# amp_tda2030_2ch_otl.net
KiCad netlist of a schematic drawn in EAGLE
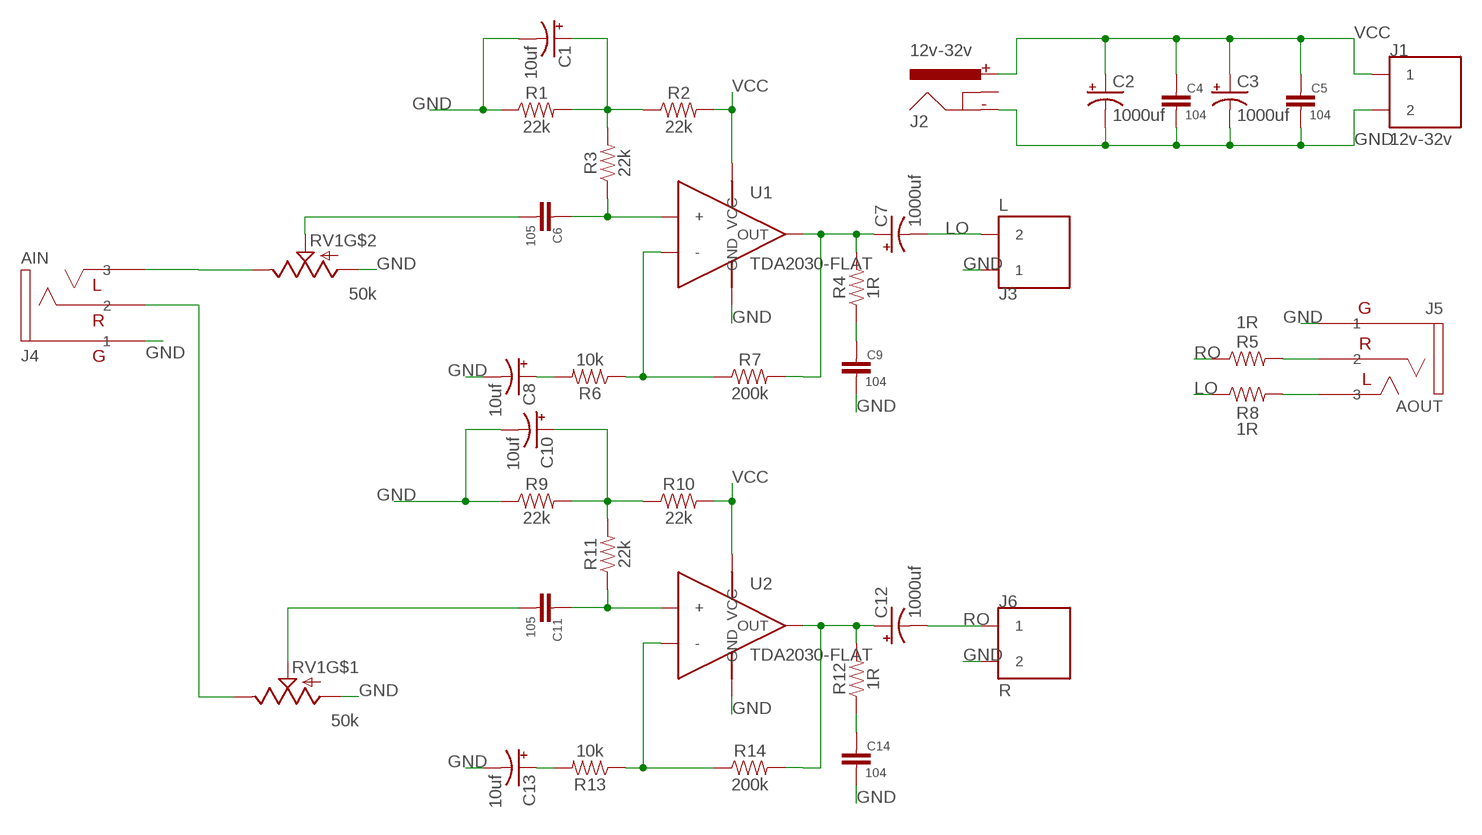
[diagram p0: schematic, sheet 1]

(export (version "E")
  (design (tool "Eeschema 10.0.6"))
  (components
    (comp (ref "C1")
      (value "10uf")
      (footprint "eagle-import:CAP_2.5MM")
      (libsource (lib "eagle-import") (part "CAP"))
    )
    (comp (ref "C2")
      (value "1000uf")
      (footprint "eagle-import:CAP_5MM_10D")
      (libsource (lib "eagle-import") (part "CAP5MM"))
    )
    (comp (ref "C3")
      (value "1000uf")
      (footprint "eagle-import:CAP_5MM_10D")
      (libsource (lib "eagle-import") (part "CAP5MM"))
    )
    (comp (ref "C4")
      (value "104")
      (footprint "eagle-import:CAP_5MM")
      (libsource (lib "eagle-import") (part "CAP_P"))
    )
    (comp (ref "C5")
      (value "104")
      (footprint "eagle-import:CAP_5MM")
      (libsource (lib "eagle-import") (part "CAP_P"))
    )
    (comp (ref "C6")
      (value "105")
      (footprint "eagle-import:CAP_5MM")
      (libsource (lib "eagle-import") (part "CAP_P"))
    )
    (comp (ref "C7")
      (value "1000uf")
      (footprint "eagle-import:CAP_5MM_10D")
      (libsource (lib "eagle-import") (part "CAP5MM"))
    )
    (comp (ref "C8")
      (value "10uf")
      (footprint "eagle-import:CAP_2.5MM")
      (libsource (lib "eagle-import") (part "CAP"))
    )
    (comp (ref "C9")
      (value "104")
      (footprint "eagle-import:CAP_5MM")
      (libsource (lib "eagle-import") (part "CAP_P"))
    )
    (comp (ref "C10")
      (value "10uf")
      (footprint "eagle-import:CAP_2.5MM")
      (libsource (lib "eagle-import") (part "CAP"))
    )
    (comp (ref "C11")
      (value "105")
      (footprint "eagle-import:CAP_5MM")
      (libsource (lib "eagle-import") (part "CAP_P"))
    )
    (comp (ref "C12")
      (value "1000uf")
      (footprint "eagle-import:CAP_5MM_10D")
      (libsource (lib "eagle-import") (part "CAP5MM"))
    )
    (comp (ref "C13")
      (value "10uf")
      (footprint "eagle-import:CAP_2.5MM")
      (libsource (lib "eagle-import") (part "CAP"))
    )
    (comp (ref "C14")
      (value "104")
      (footprint "eagle-import:CAP_5MM")
      (libsource (lib "eagle-import") (part "CAP_P"))
    )
    (comp (ref "J1")
      (value "12v-32v")
      (footprint "eagle-import:2P_5.08MM")
      (libsource (lib "eagle-import") (part "2P5.0"))
    )
    (comp (ref "J2")
      (value "12v-32v")
      (footprint "eagle-import:POWER_JACK_PTH_LOCK")
      (libsource (lib "eagle-import") (part "POWER_JACKPTH_LOCK"))
    )
    (comp (ref "J3")
      (value "L")
      (footprint "eagle-import:2P_5.08MM")
      (libsource (lib "eagle-import") (part "2P5.0"))
    )
    (comp (ref "J4")
      (value "AIN")
      (footprint "eagle-import:3.5MM")
      (libsource (lib "eagle-import") (part "3.5MM_PHONE"))
    )
    (comp (ref "J5")
      (value "AOUT")
      (footprint "eagle-import:3.5MM")
      (libsource (lib "eagle-import") (part "3.5MM_PHONE"))
    )
    (comp (ref "J6")
      (value "R")
      (footprint "eagle-import:2P_5.08MM")
      (libsource (lib "eagle-import") (part "2P5.0"))
    )
    (comp (ref "R1")
      (value "22k")
      (footprint "eagle-import:AXIAL-0.3")
      (libsource (lib "eagle-import") (part "RESISTORAXIAL-0.3"))
    )
    (comp (ref "R2")
      (value "22k")
      (footprint "eagle-import:AXIAL-0.3")
      (libsource (lib "eagle-import") (part "RESISTORAXIAL-0.3"))
    )
    (comp (ref "R3")
      (value "22k")
      (footprint "eagle-import:AXIAL-0.3")
      (libsource (lib "eagle-import") (part "RESISTORAXIAL-0.3"))
    )
    (comp (ref "R4")
      (value "1R")
      (footprint "eagle-import:AXIAL-0.3")
      (libsource (lib "eagle-import") (part "RESISTORAXIAL-0.3"))
    )
    (comp (ref "R5")
      (value "1R")
      (footprint "eagle-import:2WS")
      (libsource (lib "eagle-import") (part "RES_P"))
    )
    (comp (ref "R6")
      (value "10k")
      (footprint "eagle-import:AXIAL-0.3")
      (libsource (lib "eagle-import") (part "RESISTORAXIAL-0.3"))
    )
    (comp (ref "R7")
      (value "200k")
      (footprint "eagle-import:AXIAL-0.3")
      (libsource (lib "eagle-import") (part "RESISTORAXIAL-0.3"))
    )
    (comp (ref "R8")
      (value "1R")
      (footprint "eagle-import:2WS")
      (libsource (lib "eagle-import") (part "RES_P"))
    )
    (comp (ref "R9")
      (value "22k")
      (footprint "eagle-import:AXIAL-0.3")
      (libsource (lib "eagle-import") (part "RESISTORAXIAL-0.3"))
    )
    (comp (ref "R10")
      (value "22k")
      (footprint "eagle-import:AXIAL-0.3")
      (libsource (lib "eagle-import") (part "RESISTORAXIAL-0.3"))
    )
    (comp (ref "R11")
      (value "22k")
      (footprint "eagle-import:AXIAL-0.3")
      (libsource (lib "eagle-import") (part "RESISTORAXIAL-0.3"))
    )
    (comp (ref "R12")
      (value "1R")
      (footprint "eagle-import:AXIAL-0.3")
      (libsource (lib "eagle-import") (part "RESISTORAXIAL-0.3"))
    )
    (comp (ref "R13")
      (value "10k")
      (footprint "eagle-import:AXIAL-0.3")
      (libsource (lib "eagle-import") (part "RESISTORAXIAL-0.3"))
    )
    (comp (ref "R14")
      (value "200k")
      (footprint "eagle-import:AXIAL-0.3")
      (libsource (lib "eagle-import") (part "RESISTORAXIAL-0.3"))
    )
    (comp (ref "RV1")
      (value "50k")
      (footprint "eagle-import:POT_DUAL_GREEN")
      (libsource (lib "eagle-import") (part "POT_DUALPOT_DUAL_GREEN"))
    )
    (comp (ref "U1")
      (value "TDA2030-FLAT")
      (footprint "eagle-import:TO220-FLAT")
      (libsource (lib "eagle-import") (part "TDA2030-FLAT"))
    )
    (comp (ref "U2")
      (value "TDA2030-FLAT")
      (footprint "eagle-import:TO220-FLAT")
      (libsource (lib "eagle-import") (part "TDA2030-FLAT"))
    )
  )
  (nets
    (net (code "1") (name "/GND") (class "Default")
      (node (ref "C1") (pin "-") (pinfunction "-_-") (pintype "passive"))
      (node (ref "C10") (pin "-") (pinfunction "-_-") (pintype "passive"))
      (node (ref "C13") (pin "-") (pinfunction "-_-") (pintype "passive"))
      (node (ref "C14") (pin "P$2") (pinfunction "2_P$2") (pintype "passive"))
      (node (ref "C2") (pin "-") (pinfunction "-_-") (pintype "passive"))
      (node (ref "C3") (pin "-") (pinfunction "-_-") (pintype "passive"))
      (node (ref "C4") (pin "P$2") (pinfunction "2_P$2") (pintype "passive"))
      (node (ref "C5") (pin "P$2") (pinfunction "2_P$2") (pintype "passive"))
      (node (ref "C8") (pin "-") (pinfunction "-_-") (pintype "passive"))
      (node (ref "C9") (pin "P$2") (pinfunction "2_P$2") (pintype "passive"))
      (node (ref "J1") (pin "N") (pinfunction "2_N") (pintype "bidirectional"))
      (node (ref "J2") (pin "GND") (pinfunction "GND_GND") (pintype "bidirectional"))
      (node (ref "J3") (pin "L") (pinfunction "1_L") (pintype "bidirectional"))
      (node (ref "J4") (pin "P$1") (pinfunction "1_P$1") (pintype "bidirectional"))
      (node (ref "J5") (pin "P$1") (pinfunction "1_P$1") (pintype "bidirectional"))
      (node (ref "J6") (pin "N") (pinfunction "2_N") (pintype "bidirectional"))
      (node (ref "R1") (pin "P$1") (pinfunction "1_P$1") (pintype "passive"))
      (node (ref "R9") (pin "P$1") (pinfunction "1_P$1") (pintype "passive"))
      (node (ref "RV1") (pin "P$1") (pinfunction "A_P$1") (pintype "passive"))
      (node (ref "RV1") (pin "P$4") (pinfunction "A_P$4") (pintype "passive"))
      (node (ref "U1") (pin "3") (pinfunction "GND_3") (pintype "bidirectional"))
      (node (ref "U1") (pin "TAB") (pinfunction "GND_TAB") (pintype "bidirectional"))
      (node (ref "U2") (pin "3") (pinfunction "GND_3") (pintype "bidirectional"))
      (node (ref "U2") (pin "TAB") (pinfunction "GND_TAB") (pintype "bidirectional"))
    )
    (net (code "2") (name "/LO") (class "Default")
      (node (ref "C7") (pin "-") (pinfunction "-_-") (pintype "passive"))
      (node (ref "J3") (pin "N") (pinfunction "2_N") (pintype "bidirectional"))
      (node (ref "R8") (pin "P$1") (pinfunction "1_P$1") (pintype "passive"))
    )
    (net (code "3") (name "/RO") (class "Default")
      (node (ref "C12") (pin "-") (pinfunction "-_-") (pintype "passive"))
      (node (ref "J6") (pin "L") (pinfunction "1_L") (pintype "bidirectional"))
      (node (ref "R5") (pin "P$1") (pinfunction "1_P$1") (pintype "passive"))
    )
    (net (code "4") (name "/VCC") (class "Default")
      (node (ref "C2") (pin "+") (pinfunction "+_+") (pintype "passive"))
      (node (ref "C3") (pin "+") (pinfunction "+_+") (pintype "passive"))
      (node (ref "C4") (pin "P$1") (pinfunction "1_P$1") (pintype "passive"))
      (node (ref "C5") (pin "P$1") (pinfunction "1_P$1") (pintype "passive"))
      (node (ref "J1") (pin "L") (pinfunction "1_L") (pintype "bidirectional"))
      (node (ref "J2") (pin "PWR") (pinfunction "PWR_PWR") (pintype "bidirectional"))
      (node (ref "R10") (pin "P$2") (pinfunction "2_P$2") (pintype "passive"))
      (node (ref "R2") (pin "P$2") (pinfunction "2_P$2") (pintype "passive"))
      (node (ref "U1") (pin "5") (pinfunction "VCC_5") (pintype "bidirectional"))
      (node (ref "U2") (pin "5") (pinfunction "VCC_5") (pintype "bidirectional"))
    )
    (net (code "5") (name "Net-(C6-1)") (class "Default")
      (node (ref "C6") (pin "P$1") (pinfunction "1_P$1") (pintype "passive"))
      (node (ref "R3") (pin "P$1") (pinfunction "1_P$1") (pintype "passive"))
      (node (ref "U1") (pin "1") (pinfunction "+_1") (pintype "bidirectional"))
    )
    (net (code "6") (name "Net-(C6-2)") (class "Default")
      (node (ref "C6") (pin "P$2") (pinfunction "2_P$2") (pintype "passive"))
      (node (ref "RV1") (pin "P$5") (pinfunction "S_P$5") (pintype "passive"))
    )
    (net (code "7") (name "Net-(C9-1)") (class "Default")
      (node (ref "C9") (pin "P$1") (pinfunction "1_P$1") (pintype "passive"))
      (node (ref "R4") (pin "P$1") (pinfunction "1_P$1") (pintype "passive"))
    )
    (net (code "8") (name "Net-(C11-1)") (class "Default")
      (node (ref "C11") (pin "P$1") (pinfunction "1_P$1") (pintype "passive"))
      (node (ref "R11") (pin "P$1") (pinfunction "1_P$1") (pintype "passive"))
      (node (ref "U2") (pin "1") (pinfunction "+_1") (pintype "bidirectional"))
    )
    (net (code "9") (name "Net-(C11-2)") (class "Default")
      (node (ref "C11") (pin "P$2") (pinfunction "2_P$2") (pintype "passive"))
      (node (ref "RV1") (pin "P$2") (pinfunction "S_P$2") (pintype "passive"))
    )
    (net (code "10") (name "Net-(C14-1)") (class "Default")
      (node (ref "C14") (pin "P$1") (pinfunction "1_P$1") (pintype "passive"))
      (node (ref "R12") (pin "P$1") (pinfunction "1_P$1") (pintype "passive"))
    )
    (net (code "11") (name "Net-(J4-2)") (class "Default")
      (node (ref "J4") (pin "P$2") (pinfunction "2_P$2") (pintype "bidirectional"))
      (node (ref "RV1") (pin "P$3") (pinfunction "E_P$3") (pintype "passive"))
    )
    (net (code "12") (name "Net-(J4-3)") (class "Default")
      (node (ref "J4") (pin "P$3") (pinfunction "3_P$3") (pintype "bidirectional"))
      (node (ref "RV1") (pin "P$6") (pinfunction "E_P$6") (pintype "passive"))
    )
    (net (code "13") (name "Net-(J5-2)") (class "Default")
      (node (ref "J5") (pin "P$2") (pinfunction "2_P$2") (pintype "bidirectional"))
      (node (ref "R5") (pin "P$2") (pinfunction "2_P$2") (pintype "passive"))
    )
    (net (code "14") (name "Net-(J5-3)") (class "Default")
      (node (ref "J5") (pin "P$3") (pinfunction "3_P$3") (pintype "bidirectional"))
      (node (ref "R8") (pin "P$2") (pinfunction "2_P$2") (pintype "passive"))
    )
    (net (code "15") (name "Net-(R1-2)") (class "Default")
      (node (ref "C1") (pin "+") (pinfunction "+_+") (pintype "passive"))
      (node (ref "R1") (pin "P$2") (pinfunction "2_P$2") (pintype "passive"))
      (node (ref "R2") (pin "P$1") (pinfunction "1_P$1") (pintype "passive"))
      (node (ref "R3") (pin "P$2") (pinfunction "2_P$2") (pintype "passive"))
    )
    (net (code "16") (name "Net-(R4-2)") (class "Default")
      (node (ref "C7") (pin "+") (pinfunction "+_+") (pintype "passive"))
      (node (ref "R4") (pin "P$2") (pinfunction "2_P$2") (pintype "passive"))
      (node (ref "R7") (pin "P$2") (pinfunction "2_P$2") (pintype "passive"))
      (node (ref "U1") (pin "4") (pinfunction "OUT_4") (pintype "bidirectional"))
    )
    (net (code "17") (name "Net-(R6-1)") (class "Default")
      (node (ref "R6") (pin "P$1") (pinfunction "1_P$1") (pintype "passive"))
      (node (ref "R7") (pin "P$1") (pinfunction "1_P$1") (pintype "passive"))
      (node (ref "U1") (pin "2") (pinfunction "-_2") (pintype "bidirectional"))
    )
    (net (code "18") (name "Net-(R6-2)") (class "Default")
      (node (ref "C8") (pin "+") (pinfunction "+_+") (pintype "passive"))
      (node (ref "R6") (pin "P$2") (pinfunction "2_P$2") (pintype "passive"))
    )
    (net (code "19") (name "Net-(R10-1)") (class "Default")
      (node (ref "C10") (pin "+") (pinfunction "+_+") (pintype "passive"))
      (node (ref "R10") (pin "P$1") (pinfunction "1_P$1") (pintype "passive"))
      (node (ref "R11") (pin "P$2") (pinfunction "2_P$2") (pintype "passive"))
      (node (ref "R9") (pin "P$2") (pinfunction "2_P$2") (pintype "passive"))
    )
    (net (code "20") (name "Net-(R12-2)") (class "Default")
      (node (ref "C12") (pin "+") (pinfunction "+_+") (pintype "passive"))
      (node (ref "R12") (pin "P$2") (pinfunction "2_P$2") (pintype "passive"))
      (node (ref "R14") (pin "P$2") (pinfunction "2_P$2") (pintype "passive"))
      (node (ref "U2") (pin "4") (pinfunction "OUT_4") (pintype "bidirectional"))
    )
    (net (code "21") (name "Net-(R13-1)") (class "Default")
      (node (ref "R13") (pin "P$1") (pinfunction "1_P$1") (pintype "passive"))
      (node (ref "R14") (pin "P$1") (pinfunction "1_P$1") (pintype "passive"))
      (node (ref "U2") (pin "2") (pinfunction "-_2") (pintype "bidirectional"))
    )
    (net (code "22") (name "Net-(R13-2)") (class "Default")
      (node (ref "C13") (pin "+") (pinfunction "+_+") (pintype "passive"))
      (node (ref "R13") (pin "P$2") (pinfunction "2_P$2") (pintype "passive"))
    )
    (net (code "23") (name "unconnected-(J2-PadGNDBREAK)") (class "Default")
      (node (ref "J2") (pin "GNDBREAK") (pinfunction "GNDBREAK_GNDBREAK") (pintype "bidirectional"))
    )
  )
)
